# 15-M2_GNSS.net
KiCad netlist of a schematic drawn in Altium Designer
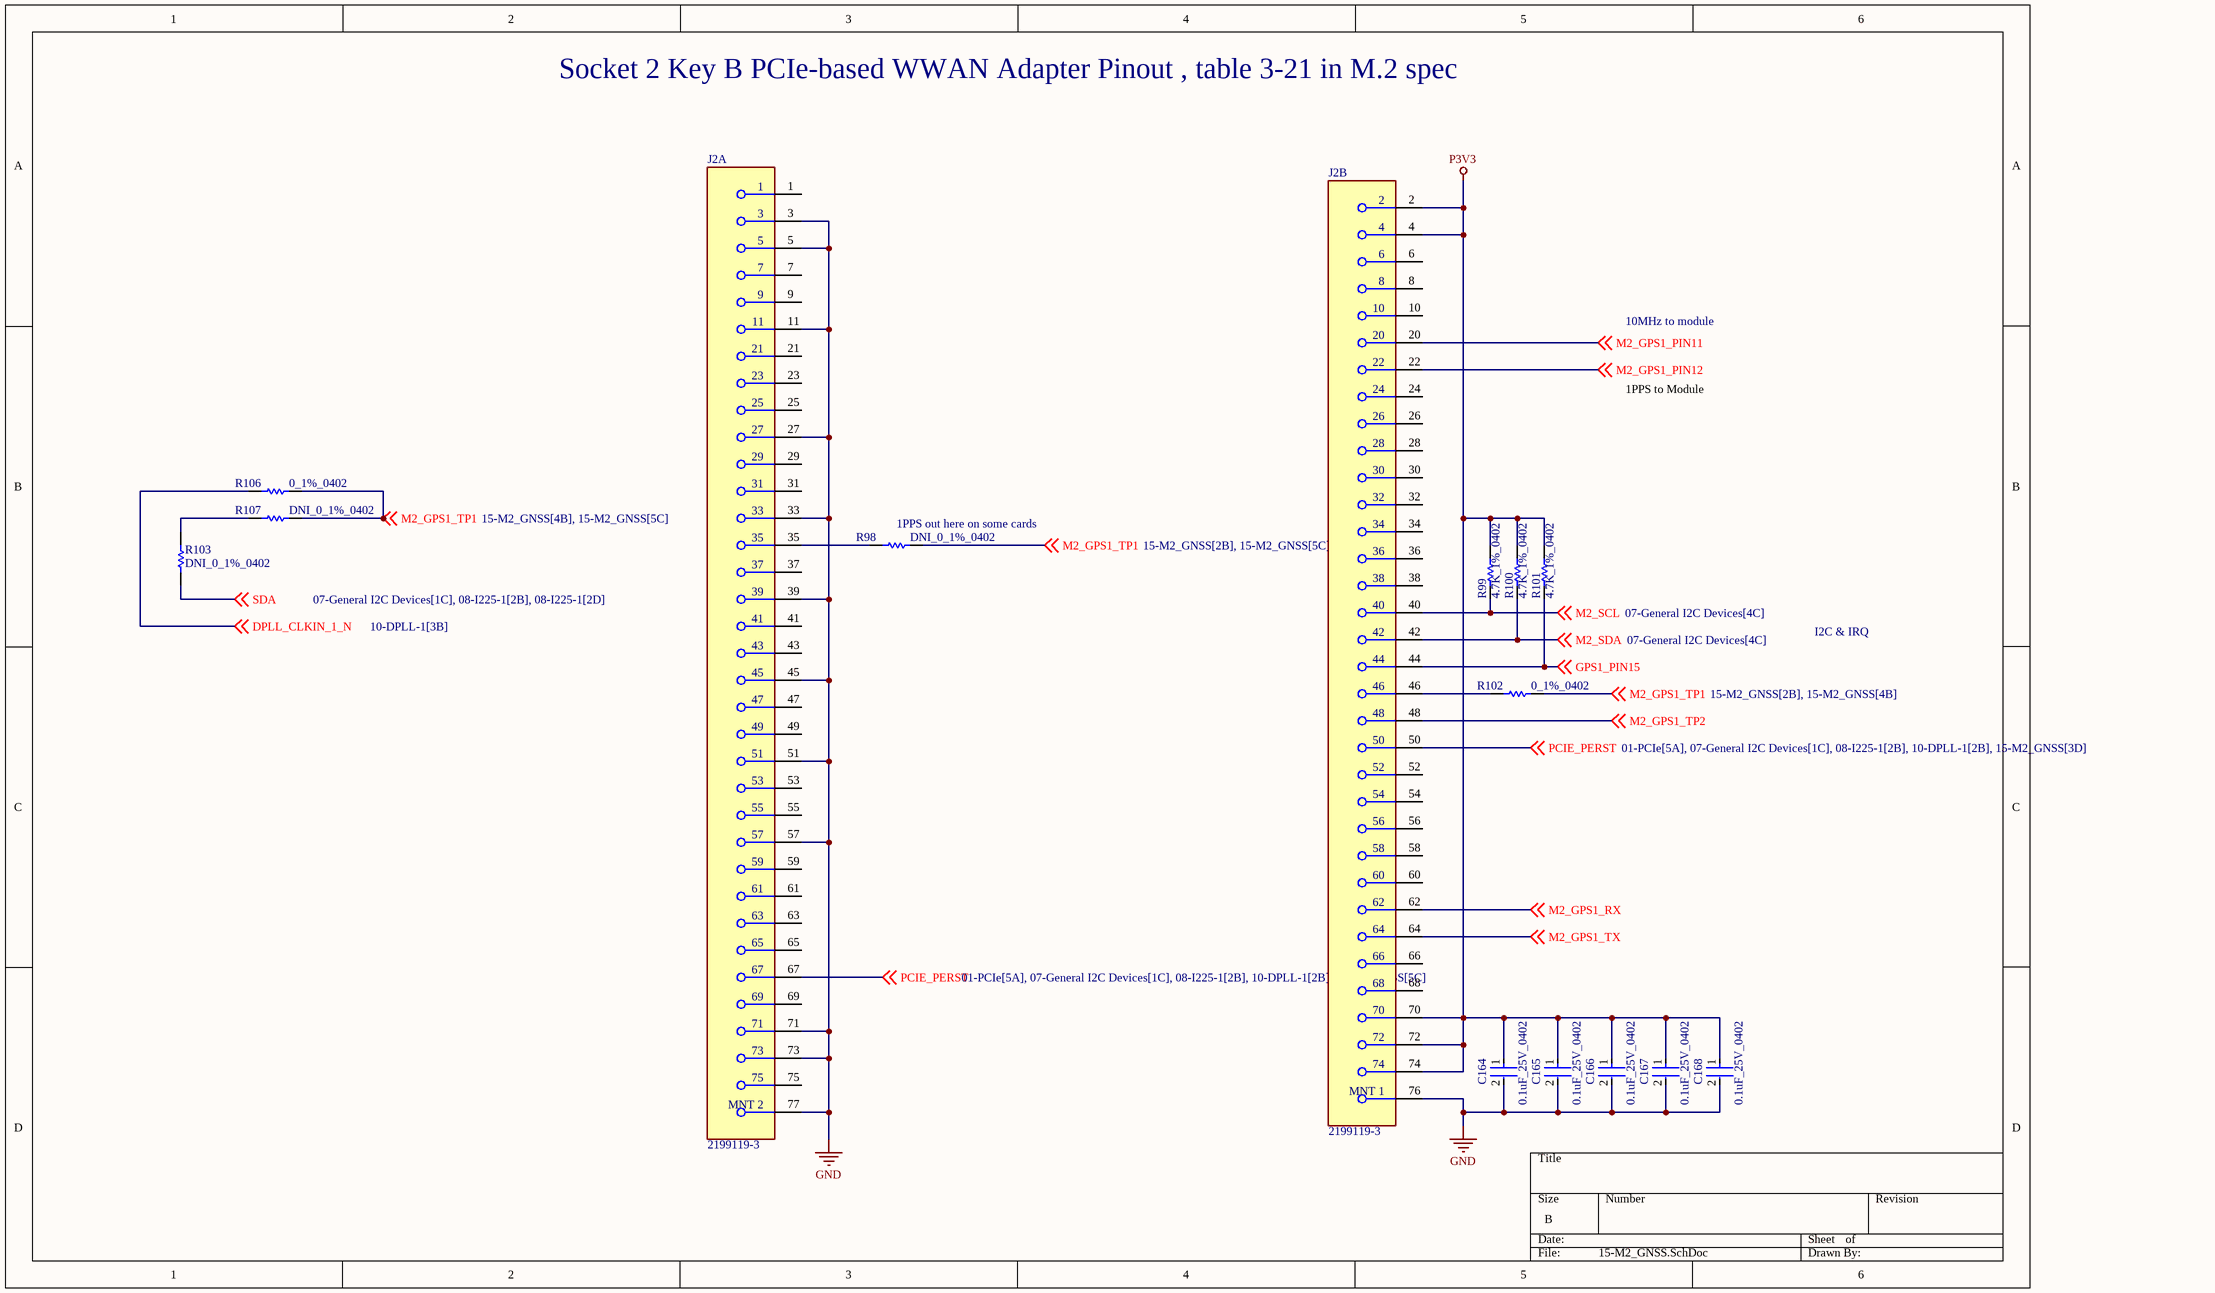
[diagram p0: 15-M2_GNSS.SchDoc]

(export (version "E")
  (design (tool "Eeschema 10.0.6"))
  (components
    (comp (ref "C164")
      (value "0.1uF_25V_0402")
      (footprint "FP-0402-L_1_0_1-W_0_5_0_1-IPC_C")
      (description "General Purpose Ceramic Capacitor, 0402, 100nF, 10%, X7R, 15%, 25V")
      (fields (field (name "VOLTAGE") "25V") (field (name "TOLERANCE") "10%"))
      (libsource (lib "Altium Content Vault") (part "b4654b650e69147ec39a6b967a45e02"))
    )
    (comp (ref "C165")
      (value "0.1uF_25V_0402")
      (footprint "FP-0402-L_1_0_1-W_0_5_0_1-IPC_C")
      (description "General Purpose Ceramic Capacitor, 0402, 100nF, 10%, X7R, 15%, 25V")
      (fields (field (name "VOLTAGE") "25V") (field (name "TOLERANCE") "10%"))
      (libsource (lib "Altium Content Vault") (part "b4654b650e69147ec39a6b967a45e02"))
    )
    (comp (ref "C166")
      (value "0.1uF_25V_0402")
      (footprint "FP-0402-L_1_0_1-W_0_5_0_1-IPC_C")
      (description "General Purpose Ceramic Capacitor, 0402, 100nF, 10%, X7R, 15%, 25V")
      (fields (field (name "VOLTAGE") "25V") (field (name "TOLERANCE") "10%"))
      (libsource (lib "Altium Content Vault") (part "b4654b650e69147ec39a6b967a45e02"))
    )
    (comp (ref "C167")
      (value "0.1uF_25V_0402")
      (footprint "FP-0402-L_1_0_1-W_0_5_0_1-IPC_C")
      (description "General Purpose Ceramic Capacitor, 0402, 100nF, 10%, X7R, 15%, 25V")
      (fields (field (name "VOLTAGE") "25V") (field (name "TOLERANCE") "10%"))
      (libsource (lib "Altium Content Vault") (part "b4654b650e69147ec39a6b967a45e02"))
    )
    (comp (ref "C168")
      (value "0.1uF_25V_0402")
      (footprint "FP-0402-L_1_0_1-W_0_5_0_1-IPC_C")
      (description "General Purpose Ceramic Capacitor, 0402, 100nF, 10%, X7R, 15%, 25V")
      (fields (field (name "VOLTAGE") "25V") (field (name "TOLERANCE") "10%"))
      (libsource (lib "Altium Content Vault") (part "b4654b650e69147ec39a6b967a45e02"))
    )
    (comp (ref "J2")
      (value "2199119-3")
      (footprint "FP-2199119-3-MFG")
      (description "CONN M.2 FEMALE 67POS 0.020 GOLD")
      (libsource (lib "Altium Content Vault") (part "a14843ccfa78e5d0b739856168502fb"))
    )
    (comp (ref "R98")
      (value "DNI_0_1%_0402")
      (footprint "RESC1005X40X25LL05T05")
      (description "Chip Resistor, 0 Ohm, 0.1 W, -55 to 155 degC, 0402 (1005 Metric), RoHS, Tape and Reel")
      (fields (field (name "MANUFACTURER") "Panasonic") (field (name "TOLERANCE") "5%"))
      (libsource (lib "Altium Content Vault") (part "RES-2"))
    )
    (comp (ref "R99")
      (value "4.7K_1%_0402")
      (footprint "RESC1005X40X25NL10T10")
      (fields (field (name "MANUFACTURER") "Bourns") (field (name "PART NUMBER") "CR0402-FX-4701GLF"))
      (libsource (lib "Altium Content Vault") (part "RES"))
    )
    (comp (ref "R100")
      (value "4.7K_1%_0402")
      (footprint "RESC1005X40X25NL10T10")
      (fields (field (name "MANUFACTURER") "Bourns") (field (name "PART NUMBER") "CR0402-FX-4701GLF"))
      (libsource (lib "Altium Content Vault") (part "RES"))
    )
    (comp (ref "R101")
      (value "4.7K_1%_0402")
      (footprint "RESC1005X40X25NL10T10")
      (fields (field (name "MANUFACTURER") "Bourns") (field (name "PART NUMBER") "CR0402-FX-4701GLF"))
      (libsource (lib "Altium Content Vault") (part "RES"))
    )
    (comp (ref "R102")
      (value "0_1%_0402")
      (footprint "RESC1005X40X25LL05T05")
      (description "Chip Resistor, 0 Ohm, 0.1 W, -55 to 155 degC, 0402 (1005 Metric), RoHS, Tape and Reel")
      (fields (field (name "MANUFACTURER") "Panasonic") (field (name "TOLERANCE") "5%"))
      (libsource (lib "Altium Content Vault") (part "RES-2"))
    )
    (comp (ref "R103")
      (value "DNI_0_1%_0402")
      (footprint "RESC1005X40X25LL05T05")
      (description "Chip Resistor, 0 Ohm, 0.1 W, -55 to 155 degC, 0402 (1005 Metric), RoHS, Tape and Reel")
      (fields (field (name "MANUFACTURER") "Panasonic") (field (name "TOLERANCE") "5%"))
      (libsource (lib "Altium Content Vault") (part "RES-2"))
    )
    (comp (ref "R106")
      (value "0_1%_0402")
      (footprint "RESC1005X40X25LL05T05")
      (description "Chip Resistor, 0 Ohm, 0.1 W, -55 to 155 degC, 0402 (1005 Metric), RoHS, Tape and Reel")
      (fields (field (name "MANUFACTURER") "Panasonic") (field (name "TOLERANCE") "5%"))
      (libsource (lib "Altium Content Vault") (part "RES-2"))
    )
    (comp (ref "R107")
      (value "DNI_0_1%_0402")
      (footprint "RESC1005X40X25LL05T05")
      (description "Chip Resistor, 0 Ohm, 0.1 W, -55 to 155 degC, 0402 (1005 Metric), RoHS, Tape and Reel")
      (fields (field (name "MANUFACTURER") "Panasonic") (field (name "TOLERANCE") "5%"))
      (libsource (lib "Altium Content Vault") (part "RES-2"))
    )
  )
  (nets
    (net (code "1") (name "DPLL_CLKIN_1_N") (class "Default")
      (node (ref "R106") (pin "1") (pinfunction "1_1") (pintype "passive"))
    )
    (net (code "2") (name "GND") (class "Default")
      (node (ref "C164") (pin "2") (pinfunction "2_2") (pintype "passive"))
      (node (ref "C165") (pin "2") (pinfunction "2_2") (pintype "passive"))
      (node (ref "C166") (pin "2") (pinfunction "2_2") (pintype "passive"))
      (node (ref "C167") (pin "2") (pinfunction "2_2") (pintype "passive"))
      (node (ref "C168") (pin "2") (pinfunction "2_2") (pintype "passive"))
      (node (ref "J2") (pin "11") (pinfunction "11_11") (pintype "passive"))
      (node (ref "J2") (pin "27") (pinfunction "27_27") (pintype "passive"))
      (node (ref "J2") (pin "3") (pinfunction "3_3") (pintype "passive"))
      (node (ref "J2") (pin "33") (pinfunction "33_33") (pintype "passive"))
      (node (ref "J2") (pin "39") (pinfunction "39_39") (pintype "passive"))
      (node (ref "J2") (pin "45") (pinfunction "45_45") (pintype "passive"))
      (node (ref "J2") (pin "5") (pinfunction "5_5") (pintype "passive"))
      (node (ref "J2") (pin "51") (pinfunction "51_51") (pintype "passive"))
      (node (ref "J2") (pin "57") (pinfunction "57_57") (pintype "passive"))
      (node (ref "J2") (pin "71") (pinfunction "71_71") (pintype "passive"))
      (node (ref "J2") (pin "73") (pinfunction "73_73") (pintype "passive"))
      (node (ref "J2") (pin "76") (pinfunction "MNT_1_76") (pintype "passive"))
      (node (ref "J2") (pin "77") (pinfunction "MNT_2_77") (pintype "passive"))
    )
    (net (code "3") (name "GPS1_PIN15") (class "Default")
      (node (ref "J2") (pin "44") (pinfunction "44_44") (pintype "passive"))
      (node (ref "R101") (pin "1") (pinfunction "1_1") (pintype "passive"))
    )
    (net (code "4") (name "M2_GPS1_PIN11") (class "Default")
      (node (ref "J2") (pin "20") (pinfunction "20_20") (pintype "passive"))
    )
    (net (code "5") (name "M2_GPS1_PIN12") (class "Default")
      (node (ref "J2") (pin "22") (pinfunction "22_22") (pintype "passive"))
    )
    (net (code "6") (name "M2_GPS1_RX") (class "Default")
      (node (ref "J2") (pin "62") (pinfunction "62_62") (pintype "passive"))
    )
    (net (code "7") (name "M2_GPS1_TP1") (class "Default")
      (node (ref "R102") (pin "2") (pinfunction "2_2") (pintype "passive"))
      (node (ref "R106") (pin "2") (pinfunction "2_2") (pintype "passive"))
      (node (ref "R107") (pin "2") (pinfunction "2_2") (pintype "passive"))
      (node (ref "R98") (pin "2") (pinfunction "2_2") (pintype "passive"))
    )
    (net (code "8") (name "M2_GPS1_TP2") (class "Default")
      (node (ref "J2") (pin "48") (pinfunction "48_48") (pintype "passive"))
    )
    (net (code "9") (name "M2_GPS1_TX") (class "Default")
      (node (ref "J2") (pin "64") (pinfunction "64_64") (pintype "passive"))
    )
    (net (code "10") (name "M2_SCL") (class "Default")
      (node (ref "J2") (pin "40") (pinfunction "40_40") (pintype "passive"))
      (node (ref "R99") (pin "1") (pinfunction "1_1") (pintype "passive"))
    )
    (net (code "11") (name "M2_SDA") (class "Default")
      (node (ref "J2") (pin "42") (pinfunction "42_42") (pintype "passive"))
      (node (ref "R100") (pin "1") (pinfunction "1_1") (pintype "passive"))
    )
    (net (code "12") (name "Net-(J2-Pad35)") (class "Default")
      (node (ref "J2") (pin "35") (pinfunction "35_35") (pintype "passive"))
      (node (ref "R98") (pin "1") (pinfunction "1_1") (pintype "passive"))
    )
    (net (code "13") (name "Net-(J2-Pad46)") (class "Default")
      (node (ref "J2") (pin "46") (pinfunction "46_46") (pintype "passive"))
      (node (ref "R102") (pin "1") (pinfunction "1_1") (pintype "passive"))
    )
    (net (code "14") (name "Net-(R103-Pad2)") (class "Default")
      (node (ref "R103") (pin "2") (pinfunction "2_2") (pintype "passive"))
      (node (ref "R107") (pin "1") (pinfunction "1_1") (pintype "passive"))
    )
    (net (code "15") (name "P3V3") (class "Default")
      (node (ref "C164") (pin "1") (pinfunction "1_1") (pintype "passive"))
      (node (ref "C165") (pin "1") (pinfunction "1_1") (pintype "passive"))
      (node (ref "C166") (pin "1") (pinfunction "1_1") (pintype "passive"))
      (node (ref "C167") (pin "1") (pinfunction "1_1") (pintype "passive"))
      (node (ref "C168") (pin "1") (pinfunction "1_1") (pintype "passive"))
      (node (ref "J2") (pin "2") (pinfunction "2_2") (pintype "passive"))
      (node (ref "J2") (pin "4") (pinfunction "4_4") (pintype "passive"))
      (node (ref "J2") (pin "70") (pinfunction "70_70") (pintype "passive"))
      (node (ref "J2") (pin "72") (pinfunction "72_72") (pintype "passive"))
      (node (ref "J2") (pin "74") (pinfunction "74_74") (pintype "passive"))
      (node (ref "R100") (pin "2") (pinfunction "2_2") (pintype "passive"))
      (node (ref "R101") (pin "2") (pinfunction "2_2") (pintype "passive"))
      (node (ref "R99") (pin "2") (pinfunction "2_2") (pintype "passive"))
    )
    (net (code "16") (name "PCIE_PERST") (class "Default")
      (node (ref "J2") (pin "50") (pinfunction "50_50") (pintype "passive"))
      (node (ref "J2") (pin "67") (pinfunction "67_67") (pintype "passive"))
    )
    (net (code "17") (name "SDA") (class "Default")
      (node (ref "R103") (pin "1") (pinfunction "1_1") (pintype "passive"))
    )
    (net (code "18") (name "unconnected-(J2-Pad1)") (class "Default")
      (node (ref "J2") (pin "1") (pinfunction "1_1") (pintype "passive"))
    )
    (net (code "19") (name "unconnected-(J2-Pad6)") (class "Default")
      (node (ref "J2") (pin "6") (pinfunction "6_6") (pintype "passive"))
    )
    (net (code "20") (name "unconnected-(J2-Pad7)") (class "Default")
      (node (ref "J2") (pin "7") (pinfunction "7_7") (pintype "passive"))
    )
    (net (code "21") (name "unconnected-(J2-Pad8)") (class "Default")
      (node (ref "J2") (pin "8") (pinfunction "8_8") (pintype "passive"))
    )
    (net (code "22") (name "unconnected-(J2-Pad9)") (class "Default")
      (node (ref "J2") (pin "9") (pinfunction "9_9") (pintype "passive"))
    )
    (net (code "23") (name "unconnected-(J2-Pad10)") (class "Default")
      (node (ref "J2") (pin "10") (pinfunction "10_10") (pintype "passive"))
    )
    (net (code "24") (name "unconnected-(J2-Pad21)") (class "Default")
      (node (ref "J2") (pin "21") (pinfunction "21_21") (pintype "passive"))
    )
    (net (code "25") (name "unconnected-(J2-Pad23)") (class "Default")
      (node (ref "J2") (pin "23") (pinfunction "23_23") (pintype "passive"))
    )
    (net (code "26") (name "unconnected-(J2-Pad24)") (class "Default")
      (node (ref "J2") (pin "24") (pinfunction "24_24") (pintype "passive"))
    )
    (net (code "27") (name "unconnected-(J2-Pad25)") (class "Default")
      (node (ref "J2") (pin "25") (pinfunction "25_25") (pintype "passive"))
    )
    (net (code "28") (name "unconnected-(J2-Pad26)") (class "Default")
      (node (ref "J2") (pin "26") (pinfunction "26_26") (pintype "passive"))
    )
    (net (code "29") (name "unconnected-(J2-Pad28)") (class "Default")
      (node (ref "J2") (pin "28") (pinfunction "28_28") (pintype "passive"))
    )
    (net (code "30") (name "unconnected-(J2-Pad29)") (class "Default")
      (node (ref "J2") (pin "29") (pinfunction "29_29") (pintype "passive"))
    )
    (net (code "31") (name "unconnected-(J2-Pad30)") (class "Default")
      (node (ref "J2") (pin "30") (pinfunction "30_30") (pintype "passive"))
    )
    (net (code "32") (name "unconnected-(J2-Pad31)") (class "Default")
      (node (ref "J2") (pin "31") (pinfunction "31_31") (pintype "passive"))
    )
    (net (code "33") (name "unconnected-(J2-Pad32)") (class "Default")
      (node (ref "J2") (pin "32") (pinfunction "32_32") (pintype "passive"))
    )
    (net (code "34") (name "unconnected-(J2-Pad34)") (class "Default")
      (node (ref "J2") (pin "34") (pinfunction "34_34") (pintype "passive"))
    )
    (net (code "35") (name "unconnected-(J2-Pad36)") (class "Default")
      (node (ref "J2") (pin "36") (pinfunction "36_36") (pintype "passive"))
    )
    (net (code "36") (name "unconnected-(J2-Pad37)") (class "Default")
      (node (ref "J2") (pin "37") (pinfunction "37_37") (pintype "passive"))
    )
    (net (code "37") (name "unconnected-(J2-Pad38)") (class "Default")
      (node (ref "J2") (pin "38") (pinfunction "38_38") (pintype "passive"))
    )
    (net (code "38") (name "unconnected-(J2-Pad41)") (class "Default")
      (node (ref "J2") (pin "41") (pinfunction "41_41") (pintype "passive"))
    )
    (net (code "39") (name "unconnected-(J2-Pad43)") (class "Default")
      (node (ref "J2") (pin "43") (pinfunction "43_43") (pintype "passive"))
    )
    (net (code "40") (name "unconnected-(J2-Pad47)") (class "Default")
      (node (ref "J2") (pin "47") (pinfunction "47_47") (pintype "passive"))
    )
    (net (code "41") (name "unconnected-(J2-Pad49)") (class "Default")
      (node (ref "J2") (pin "49") (pinfunction "49_49") (pintype "passive"))
    )
    (net (code "42") (name "unconnected-(J2-Pad52)") (class "Default")
      (node (ref "J2") (pin "52") (pinfunction "52_52") (pintype "passive"))
    )
    (net (code "43") (name "unconnected-(J2-Pad53)") (class "Default")
      (node (ref "J2") (pin "53") (pinfunction "53_53") (pintype "passive"))
    )
    (net (code "44") (name "unconnected-(J2-Pad54)") (class "Default")
      (node (ref "J2") (pin "54") (pinfunction "54_54") (pintype "passive"))
    )
    (net (code "45") (name "unconnected-(J2-Pad55)") (class "Default")
      (node (ref "J2") (pin "55") (pinfunction "55_55") (pintype "passive"))
    )
    (net (code "46") (name "unconnected-(J2-Pad56)") (class "Default")
      (node (ref "J2") (pin "56") (pinfunction "56_56") (pintype "passive"))
    )
    (net (code "47") (name "unconnected-(J2-Pad58)") (class "Default")
      (node (ref "J2") (pin "58") (pinfunction "58_58") (pintype "passive"))
    )
    (net (code "48") (name "unconnected-(J2-Pad59)") (class "Default")
      (node (ref "J2") (pin "59") (pinfunction "59_59") (pintype "passive"))
    )
    (net (code "49") (name "unconnected-(J2-Pad60)") (class "Default")
      (node (ref "J2") (pin "60") (pinfunction "60_60") (pintype "passive"))
    )
    (net (code "50") (name "unconnected-(J2-Pad61)") (class "Default")
      (node (ref "J2") (pin "61") (pinfunction "61_61") (pintype "passive"))
    )
    (net (code "51") (name "unconnected-(J2-Pad63)") (class "Default")
      (node (ref "J2") (pin "63") (pinfunction "63_63") (pintype "passive"))
    )
    (net (code "52") (name "unconnected-(J2-Pad65)") (class "Default")
      (node (ref "J2") (pin "65") (pinfunction "65_65") (pintype "passive"))
    )
    (net (code "53") (name "unconnected-(J2-Pad66)") (class "Default")
      (node (ref "J2") (pin "66") (pinfunction "66_66") (pintype "passive"))
    )
    (net (code "54") (name "unconnected-(J2-Pad68)") (class "Default")
      (node (ref "J2") (pin "68") (pinfunction "68_68") (pintype "passive"))
    )
    (net (code "55") (name "unconnected-(J2-Pad69)") (class "Default")
      (node (ref "J2") (pin "69") (pinfunction "69_69") (pintype "passive"))
    )
    (net (code "56") (name "unconnected-(J2-Pad75)") (class "Default")
      (node (ref "J2") (pin "75") (pinfunction "75_75") (pintype "passive"))
    )
  )
)
